# Spring_Rev2_expander.net
KiCad netlist of a schematic drawn in EAGLE
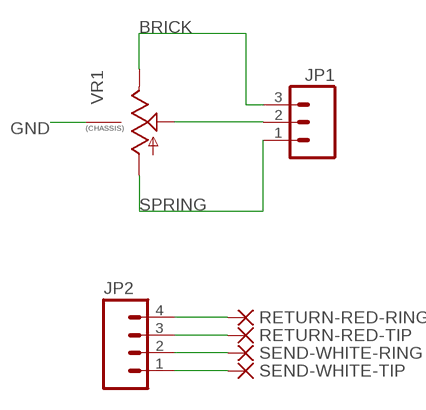
[diagram p0: schematic, sheet 1]

(export (version "E")
  (design (tool "Eeschema 10.0.6"))
  (components
    (comp (ref "JP1")
      (value "M03POLAR_LOCK")
      (footprint "eagle-import:MOLEX-1X3_LOCK")
      (libsource (lib "eagle-import") (part "M03POLAR_LOCK"))
    )
    (comp (ref "JP2")
      (value "M04POLAR_LOCK")
      (footprint "eagle-import:MOLEX-1X4_LOCK")
      (libsource (lib "eagle-import") (part "M04POLAR_LOCK"))
    )
    (comp (ref "RETURN-RED-RING")
      (value "PAD-1.00-2.00")
      (footprint "eagle-import:PAD-1.00-2.00")
      (libsource (lib "eagle-import") (part "PAD-1.00-2.00"))
    )
    (comp (ref "RETURN-RED-TIP")
      (value "PAD-1.00-2.00")
      (footprint "eagle-import:PAD-1.00-2.00")
      (libsource (lib "eagle-import") (part "PAD-1.00-2.00"))
    )
    (comp (ref "SEND-WHITE-RING")
      (value "PAD-1.00-2.00")
      (footprint "eagle-import:PAD-1.00-2.00")
      (libsource (lib "eagle-import") (part "PAD-1.00-2.00"))
    )
    (comp (ref "SEND-WHITE-TIP")
      (value "PAD-1.00-2.00")
      (footprint "eagle-import:PAD-1.00-2.00")
      (libsource (lib "eagle-import") (part "PAD-1.00-2.00"))
    )
    (comp (ref "VR1")
      (value "9MM_SNAP-IN_POT_CHASSIS")
      (footprint "eagle-import:9MM_SNAP-IN_POT")
      (libsource (lib "eagle-import") (part "9MM_SNAP-IN_POT_CHASSIS"))
    )
  )
  (nets
    (net (code "1") (name "/BRICK") (class "Default")
      (node (ref "JP1") (pin "3") (pinfunction "3_3") (pintype "passive"))
      (node (ref "VR1") (pin "3") (pinfunction "E_3") (pintype "passive"))
    )
    (net (code "2") (name "/GND") (class "Default")
      (node (ref "JP2") (pin "4") (pinfunction "4_4") (pintype "passive"))
      (node (ref "RETURN-RED-RING") (pin "1") (pinfunction "P_1") (pintype "passive"))
      (node (ref "VR1") (pin "CHASSIS1") (pinfunction "P$1_CHASSIS1") (pintype "passive"))
      (node (ref "VR1") (pin "CHASSIS2") (pinfunction "P$1_CHASSIS2") (pintype "passive"))
    )
    (net (code "3") (name "/SPRING") (class "Default")
      (node (ref "JP1") (pin "1") (pinfunction "1_1") (pintype "passive"))
      (node (ref "VR1") (pin "1") (pinfunction "A_1") (pintype "passive"))
    )
    (net (code "4") (name "Net-(RETURN-RED-TIP-P)") (class "Default")
      (node (ref "JP2") (pin "3") (pinfunction "3_3") (pintype "passive"))
      (node (ref "RETURN-RED-TIP") (pin "1") (pinfunction "P_1") (pintype "passive"))
    )
    (net (code "5") (name "Net-(SEND-WHITE-RING-P)") (class "Default")
      (node (ref "JP2") (pin "2") (pinfunction "2_2") (pintype "passive"))
      (node (ref "SEND-WHITE-RING") (pin "1") (pinfunction "P_1") (pintype "passive"))
    )
    (net (code "6") (name "Net-(SEND-WHITE-TIP-P)") (class "Default")
      (node (ref "JP2") (pin "1") (pinfunction "1_1") (pintype "passive"))
      (node (ref "SEND-WHITE-TIP") (pin "1") (pinfunction "P_1") (pintype "passive"))
    )
    (net (code "7") (name "Net-(VR1-S)") (class "Default")
      (node (ref "JP1") (pin "2") (pinfunction "2_2") (pintype "passive"))
      (node (ref "VR1") (pin "2") (pinfunction "S_2") (pintype "passive"))
    )
  )
)
